# 60-hv-amp-digital-switching.net
KiCad netlist of a schematic drawn in EAGLE
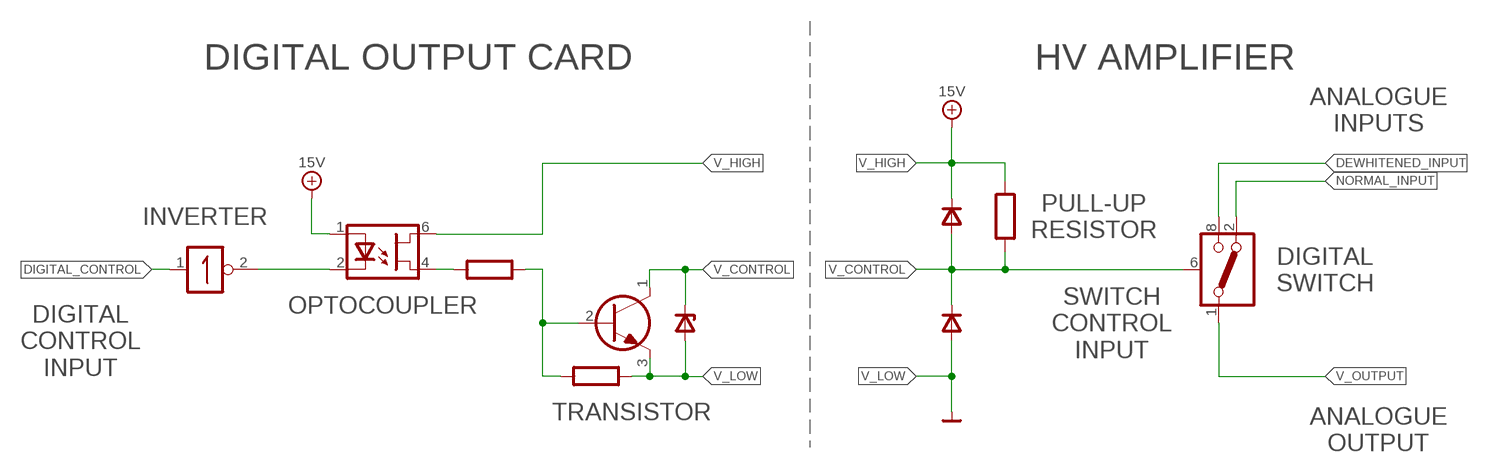
[diagram p0: schematic, sheet 1]

(export (version "E")
  (design (tool "Eeschema 10.0.6"))
  (components
    (comp (ref "D1")
      (value "DZ")
      (footprint "eagle-import:DZ04N")
      (libsource (lib "eagle-import") (part "DZ"))
    )
    (comp (ref "D2")
      (value "D")
      (footprint "eagle-import:D04N-DO35-VALUE")
      (libsource (lib "eagle-import") (part "D"))
    )
    (comp (ref "D3")
      (value "D")
      (footprint "eagle-import:D04N-DO35-VALUE")
      (libsource (lib "eagle-import") (part "D"))
    )
    (comp (ref "N1")
      (value "74AC04")
      (footprint "eagle-import:DIP14L")
      (libsource (lib "eagle-import") (part "0474AC"))
    )
    (comp (ref "N2")
      (value "DG419")
      (footprint "eagle-import:DIP08L")
      (libsource (lib "eagle-import") (part "DG419"))
    )
    (comp (ref "N3")
      (value "H11F1")
      (footprint "eagle-import:DIP06L")
      (libsource (lib "eagle-import") (part "H11F1"))
    )
    (comp (ref "R1")
      (value "R")
      (footprint "eagle-import:DUMMY2")
      (libsource (lib "eagle-import") (part "R"))
    )
    (comp (ref "R2")
      (value "R")
      (footprint "eagle-import:DUMMY2")
      (libsource (lib "eagle-import") (part "R"))
    )
    (comp (ref "R3")
      (value "R")
      (footprint "eagle-import:DUMMY2")
      (libsource (lib "eagle-import") (part "R"))
    )
    (comp (ref "T1")
      (value "BC547")
      (footprint "eagle-import:TO92N")
      (libsource (lib "eagle-import") (part "BC547"))
    )
    (comp (ref "X1")
      (value "15V")
      (footprint "eagle-import:DUMMY1")
      (libsource (lib "eagle-import") (part "V+"))
    )
    (comp (ref "X2")
      (value "15V")
      (footprint "eagle-import:DUMMY1")
      (libsource (lib "eagle-import") (part "V+"))
    )
  )
  (nets
    (net (code "1") (name "DEWHITENED_INPUT") (class "Default")
      (node (ref "N2") (pin "8") (pinfunction "S2B_8") (pintype "bidirectional"))
    )
    (net (code "2") (name "DIGITAL_CONTROL") (class "Default")
      (node (ref "N1") (pin "1") (pinfunction "I_1") (pintype "input"))
    )
    (net (code "3") (name "NORMAL_INPUT") (class "Default")
      (node (ref "N2") (pin "2") (pinfunction "S2A_2") (pintype "bidirectional"))
    )
    (net (code "4") (name "Net-(N1A-O)") (class "Default")
      (node (ref "N1") (pin "2") (pinfunction "O_2") (pintype "output"))
      (node (ref "N3") (pin "2") (pinfunction "C_2") (pintype "passive"))
    )
    (net (code "5") (name "Net-(N3-A)") (class "Default")
      (node (ref "N3") (pin "1") (pinfunction "A_1") (pintype "passive"))
      (node (ref "X1") (pin "1") (pinfunction "1_1") (pintype "bidirectional"))
    )
    (net (code "6") (name "Net-(N3-R2)") (class "Default")
      (node (ref "N3") (pin "4") (pinfunction "R2_4") (pintype "passive"))
      (node (ref "R1") (pin "1") (pinfunction "N$DUMMY_1") (pintype "bidirectional"))
    )
    (net (code "7") (name "Net-(T1-B)") (class "Default")
      (node (ref "R1") (pin "2") (pinfunction "N$DUMMY_2") (pintype "bidirectional"))
      (node (ref "R2") (pin "1") (pinfunction "N$DUMMY_1") (pintype "bidirectional"))
      (node (ref "T1") (pin "2") (pinfunction "B_2") (pintype "bidirectional"))
    )
    (net (code "8") (name "V_CONTROL") (class "Default")
      (node (ref "D1") (pin "C") (pinfunction "C_C") (pintype "passive"))
      (node (ref "D2") (pin "C") (pinfunction "C_C") (pintype "passive"))
      (node (ref "D3") (pin "A") (pinfunction "A_A") (pintype "passive"))
      (node (ref "N2") (pin "6") (pinfunction "D_6") (pintype "input"))
      (node (ref "R3") (pin "1") (pinfunction "N$DUMMY_1") (pintype "bidirectional"))
      (node (ref "T1") (pin "1") (pinfunction "C_1") (pintype "bidirectional"))
    )
    (net (code "9") (name "V_HIGH") (class "Default")
      (node (ref "D3") (pin "C") (pinfunction "C_C") (pintype "passive"))
      (node (ref "N3") (pin "6") (pinfunction "R1_6") (pintype "passive"))
      (node (ref "R3") (pin "2") (pinfunction "N$DUMMY_2") (pintype "bidirectional"))
      (node (ref "X2") (pin "1") (pinfunction "1_1") (pintype "bidirectional"))
    )
    (net (code "10") (name "V_LOW") (class "Default")
      (node (ref "D1") (pin "A") (pinfunction "A_A") (pintype "passive"))
      (node (ref "D2") (pin "A") (pinfunction "A_A") (pintype "passive"))
      (node (ref "R2") (pin "2") (pinfunction "N$DUMMY_2") (pintype "bidirectional"))
      (node (ref "T1") (pin "3") (pinfunction "E_3") (pintype "bidirectional"))
    )
    (net (code "11") (name "V_OUTPUT") (class "Default")
      (node (ref "N2") (pin "1") (pinfunction "S1_1") (pintype "bidirectional"))
    )
  )
)
